# breadboard_rev06_resized-2.net
KiCad netlist of a schematic drawn in EAGLE
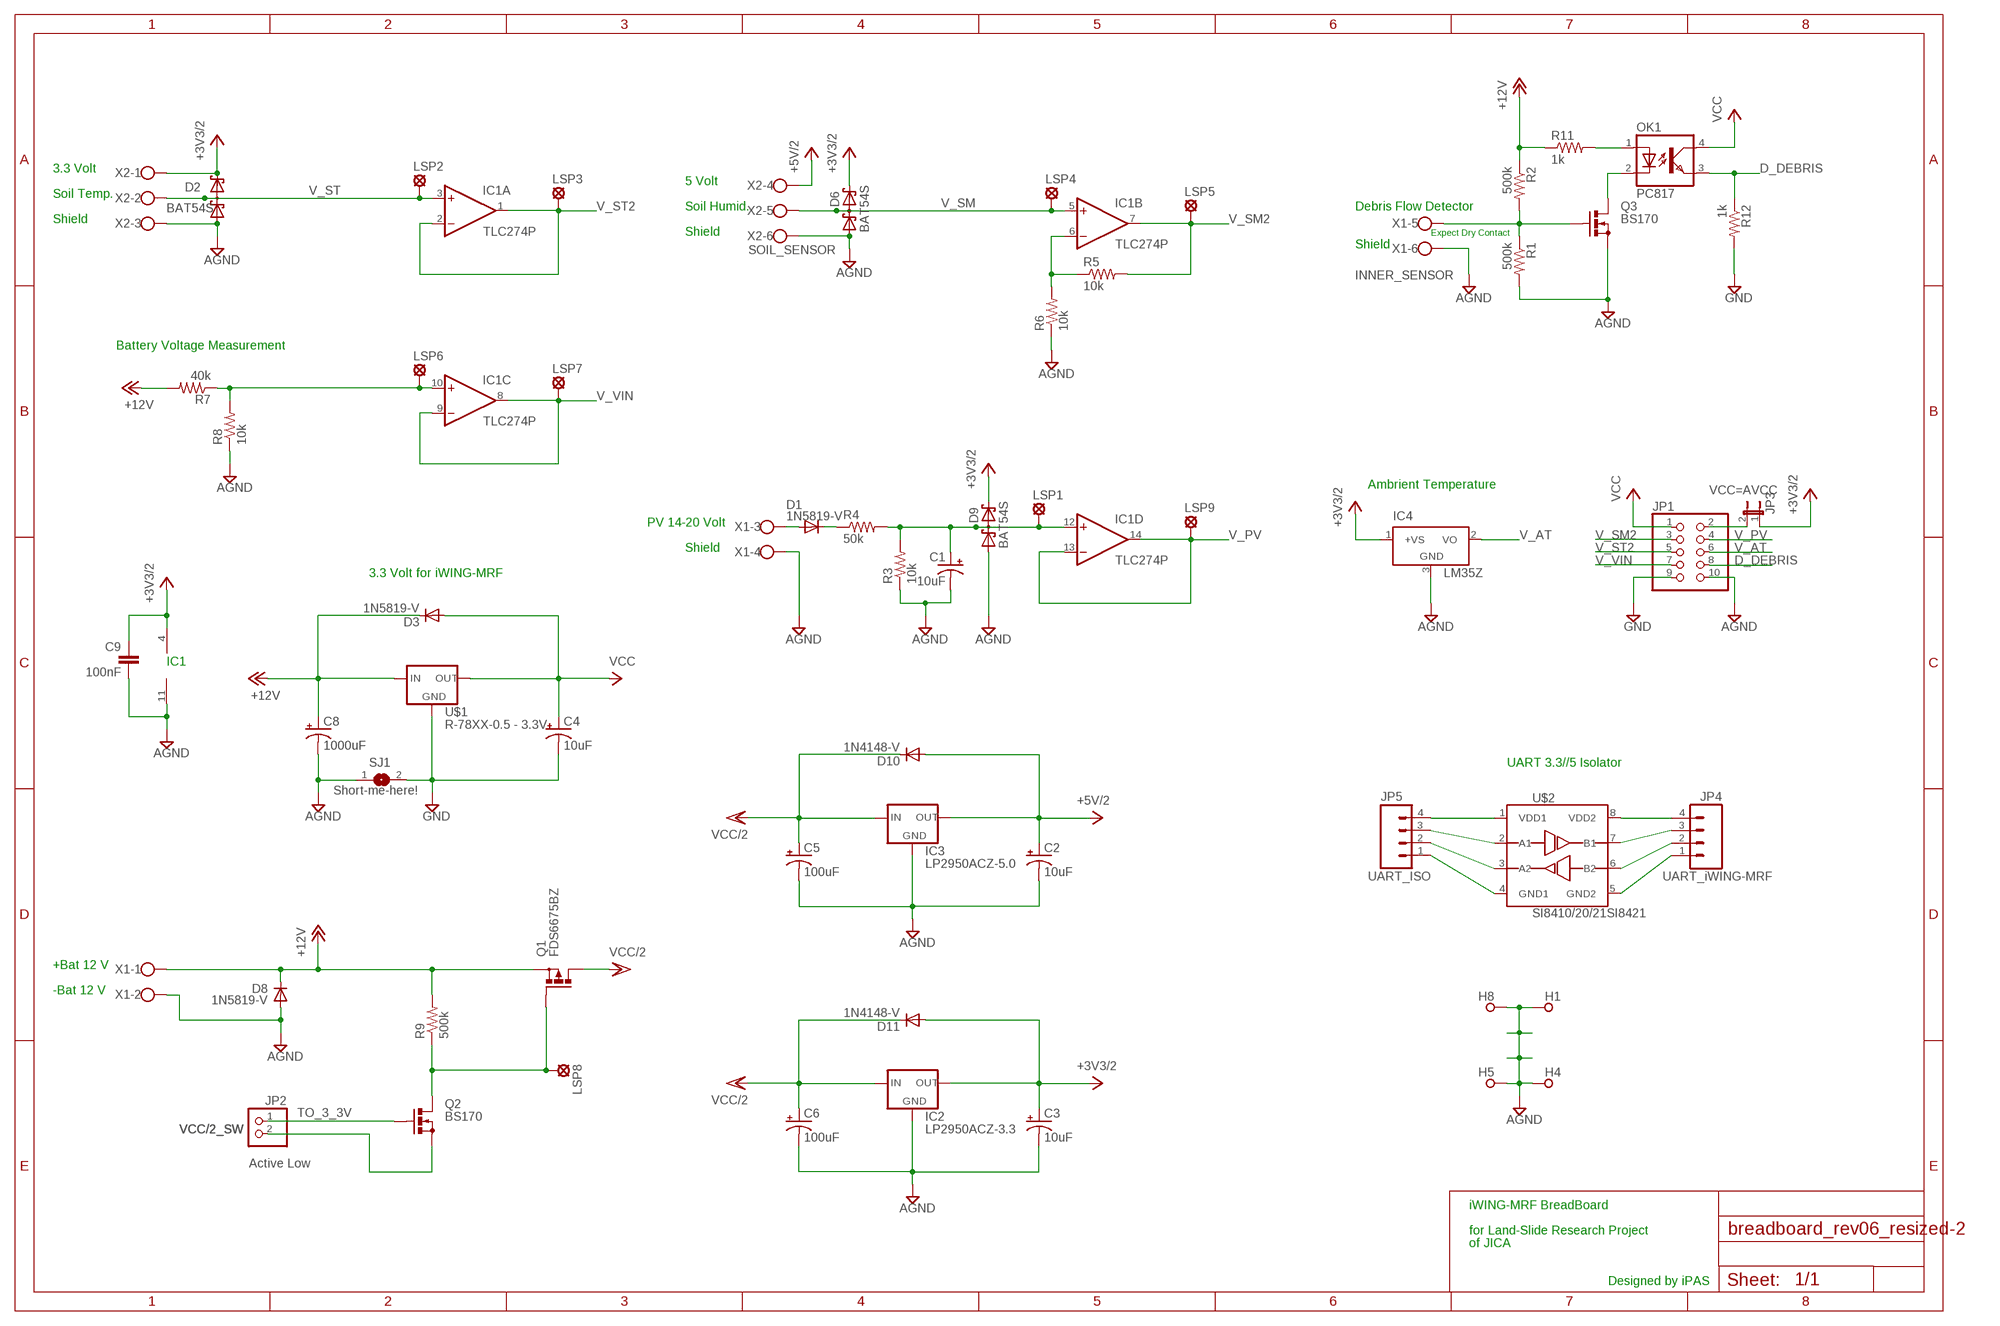
[diagram p0: schematic, sheet 1]

(export (version "E")
  (design (tool "Eeschema 10.0.6"))
  (components
    (comp (ref "C1")
      (value "10uF")
      (footprint "eagle-import:RCL_E2,5-7")
      (libsource (lib "eagle-import") (part "RCL_CPOL-USE2.5-7"))
    )
    (comp (ref "C2")
      (value "10uF")
      (footprint "eagle-import:RCL_E2,5-7")
      (libsource (lib "eagle-import") (part "RCL_CPOL-USE2.5-7"))
    )
    (comp (ref "C3")
      (value "10uF")
      (footprint "eagle-import:RCL_E2,5-7")
      (libsource (lib "eagle-import") (part "RCL_CPOL-USE2.5-7"))
    )
    (comp (ref "C4")
      (value "10uF")
      (footprint "eagle-import:RCL_E2,5-7")
      (libsource (lib "eagle-import") (part "RCL_CPOL-USE2.5-7"))
    )
    (comp (ref "C5")
      (value "100uF")
      (footprint "eagle-import:RCL_E2,5-7")
      (libsource (lib "eagle-import") (part "RCL_CPOL-USE2.5-7"))
    )
    (comp (ref "C6")
      (value "100uF")
      (footprint "eagle-import:RCL_E2,5-7")
      (libsource (lib "eagle-import") (part "RCL_CPOL-USE2.5-7"))
    )
    (comp (ref "C8")
      (value "1000uF")
      (footprint "eagle-import:RCL_E5-13")
      (libsource (lib "eagle-import") (part "RCL_CPOL-USE5-13"))
    )
    (comp (ref "C9")
      (value "100nF")
      (footprint "eagle-import:RCL_C050-025X075")
      (libsource (lib "eagle-import") (part "RCL_C-EU050-025X075"))
    )
    (comp (ref "D1")
      (value "1N5819-V")
      (footprint "eagle-import:DO41-150V")
      (libsource (lib "eagle-import") (part "1N5819-V"))
    )
    (comp (ref "D2")
      (value "BAT54S")
      (footprint "eagle-import:SOT23")
      (libsource (lib "eagle-import") (part "BAT54S"))
    )
    (comp (ref "D3")
      (value "1N5819-V")
      (footprint "eagle-import:DO41-150V")
      (libsource (lib "eagle-import") (part "1N5819-V"))
    )
    (comp (ref "D6")
      (value "BAT54S")
      (footprint "eagle-import:SOT23")
      (libsource (lib "eagle-import") (part "BAT54S"))
    )
    (comp (ref "D8")
      (value "1N5819-V")
      (footprint "eagle-import:DO41-150V")
      (libsource (lib "eagle-import") (part "1N5819-V"))
    )
    (comp (ref "D9")
      (value "BAT54S")
      (footprint "eagle-import:SOT23")
      (libsource (lib "eagle-import") (part "BAT54S"))
    )
    (comp (ref "D10")
      (value "1N4148-V")
      (footprint "eagle-import:DO35-100V")
      (libsource (lib "eagle-import") (part "1N4148-V"))
    )
    (comp (ref "D11")
      (value "1N4148-V")
      (footprint "eagle-import:DO35-100V")
      (libsource (lib "eagle-import") (part "1N4148-V"))
    )
    (comp (ref "H1")
      (value "SPECIAL_DRILL_0.1560")
      (footprint "eagle-import:PAD_0.1560")
      (libsource (lib "eagle-import") (part "SPECIAL_DRILL_0.1560"))
    )
    (comp (ref "H4")
      (value "SPECIAL_DRILL_0.1560")
      (footprint "eagle-import:PAD_0.1560")
      (libsource (lib "eagle-import") (part "SPECIAL_DRILL_0.1560"))
    )
    (comp (ref "H5")
      (value "SPECIAL_DRILL_0.1560")
      (footprint "eagle-import:PAD_0.1560")
      (libsource (lib "eagle-import") (part "SPECIAL_DRILL_0.1560"))
    )
    (comp (ref "H8")
      (value "SPECIAL_DRILL_0.1560")
      (footprint "eagle-import:PAD_0.1560")
      (libsource (lib "eagle-import") (part "SPECIAL_DRILL_0.1560"))
    )
    (comp (ref "IC1")
      (value "TLC274P")
      (footprint "eagle-import:DIL14")
      (libsource (lib "eagle-import") (part "TLC274P"))
    )
    (comp (ref "IC2")
      (value "LP2950ACZ-3.3")
      (footprint "eagle-import:TO92")
      (libsource (lib "eagle-import") (part "LP2950?ACZ-3.3"))
    )
    (comp (ref "IC3")
      (value "LP2950ACZ-5.0")
      (footprint "eagle-import:TO92")
      (libsource (lib "eagle-import") (part "LP2950?ACZ-5.0"))
    )
    (comp (ref "IC4")
      (value "LM35Z")
      (footprint "eagle-import:TO92")
      (libsource (lib "eagle-import") (part "LM35?Z"))
    )
    (comp (ref "JP1")
      (value "HEADER-2X5")
      (footprint "eagle-import:2X05")
      (libsource (lib "eagle-import") (part "HEADER-2X5"))
    )
    (comp (ref "JP2")
      (value "Active Low")
      (footprint "eagle-import:1X02")
      (libsource (lib "eagle-import") (part "PINHD-1X2"))
    )
    (comp (ref "JP3")
      (value "VCC=AVCC")
      (footprint "eagle-import:JUMPER_JP1")
      (libsource (lib "eagle-import") (part "JP1E"))
    )
    (comp (ref "JP4")
      (value "UART_iWING-MRF")
      (footprint "eagle-import:MOLEX-1X4")
      (libsource (lib "eagle-import") (part "M04POLAR"))
    )
    (comp (ref "JP5")
      (value "UART_ISO")
      (footprint "eagle-import:MOLEX-1X4")
      (libsource (lib "eagle-import") (part "M04POLAR"))
    )
    (comp (ref "LSP1")
      (value "LSP13")
      (footprint "eagle-import:LSP13")
      (libsource (lib "eagle-import") (part "LSP13"))
    )
    (comp (ref "LSP2")
      (value "LSP13")
      (footprint "eagle-import:LSP13")
      (libsource (lib "eagle-import") (part "LSP13"))
    )
    (comp (ref "LSP3")
      (value "LSP13")
      (footprint "eagle-import:LSP13")
      (libsource (lib "eagle-import") (part "LSP13"))
    )
    (comp (ref "LSP4")
      (value "LSP13")
      (footprint "eagle-import:LSP13")
      (libsource (lib "eagle-import") (part "LSP13"))
    )
    (comp (ref "LSP5")
      (value "LSP13")
      (footprint "eagle-import:LSP13")
      (libsource (lib "eagle-import") (part "LSP13"))
    )
    (comp (ref "LSP6")
      (value "LSP13")
      (footprint "eagle-import:LSP13")
      (libsource (lib "eagle-import") (part "LSP13"))
    )
    (comp (ref "LSP7")
      (value "LSP13")
      (footprint "eagle-import:LSP13")
      (libsource (lib "eagle-import") (part "LSP13"))
    )
    (comp (ref "LSP8")
      (value "LSP13")
      (footprint "eagle-import:LSP13")
      (libsource (lib "eagle-import") (part "LSP13"))
    )
    (comp (ref "LSP9")
      (value "LSP13")
      (footprint "eagle-import:LSP13")
      (libsource (lib "eagle-import") (part "LSP13"))
    )
    (comp (ref "OK1")
      (value "PC817")
      (footprint "eagle-import:DIL04")
      (fields (field (name "MPN") "PC817X4J000F"))
      (libsource (lib "eagle-import") (part "PC817"))
    )
    (comp (ref "Q1")
      (value "FDS6675BZ")
      (footprint "eagle-import:SO-08")
      (libsource (lib "eagle-import") (part "P-MOSFET-SO8"))
    )
    (comp (ref "Q2")
      (value "BS170")
      (footprint "eagle-import:SOT54E")
      (libsource (lib "eagle-import") (part "BS170"))
    )
    (comp (ref "Q3")
      (value "BS170")
      (footprint "eagle-import:SOT54E")
      (libsource (lib "eagle-import") (part "BS170"))
    )
    (comp (ref "R1")
      (value "500k")
      (footprint "eagle-import:RCL_0204_7")
      (libsource (lib "eagle-import") (part "RCL_R-US_0204/7"))
    )
    (comp (ref "R2")
      (value "500k")
      (footprint "eagle-import:RCL_0204_7")
      (libsource (lib "eagle-import") (part "RCL_R-US_0204/7"))
    )
    (comp (ref "R3")
      (value "10k")
      (footprint "eagle-import:RCL_0204_7")
      (libsource (lib "eagle-import") (part "RCL_R-US_0204/7"))
    )
    (comp (ref "R4")
      (value "50k")
      (footprint "eagle-import:RCL_0204_7")
      (libsource (lib "eagle-import") (part "RCL_R-US_0204/7"))
    )
    (comp (ref "R5")
      (value "10k")
      (footprint "eagle-import:RCL_0204_7")
      (libsource (lib "eagle-import") (part "RCL_R-US_0204/7"))
    )
    (comp (ref "R6")
      (value "10k")
      (footprint "eagle-import:RCL_0204_7")
      (libsource (lib "eagle-import") (part "RCL_R-US_0204/7"))
    )
    (comp (ref "R7")
      (value "40k")
      (footprint "eagle-import:RCL_0204_7")
      (libsource (lib "eagle-import") (part "RCL_R-US_0204/7"))
    )
    (comp (ref "R8")
      (value "10k")
      (footprint "eagle-import:RCL_0204_7")
      (libsource (lib "eagle-import") (part "RCL_R-US_0204/7"))
    )
    (comp (ref "R9")
      (value "500k")
      (footprint "eagle-import:RCL_0204_7")
      (libsource (lib "eagle-import") (part "RCL_R-US_0204/7"))
    )
    (comp (ref "R11")
      (value "1k")
      (footprint "eagle-import:RCL_0204_7")
      (libsource (lib "eagle-import") (part "RCL_R-US_0204/7"))
    )
    (comp (ref "R12")
      (value "1k")
      (footprint "eagle-import:RCL_0204_7")
      (libsource (lib "eagle-import") (part "RCL_R-US_0204/7"))
    )
    (comp (ref "SJ1")
      (value "Short-me-here!")
      (footprint "eagle-import:SJ")
      (libsource (lib "eagle-import") (part "SJ"))
    )
    (comp (ref "U$1")
      (value "R-78XX-0.5 - 3.3V")
      (footprint "eagle-import:SIP3")
      (libsource (lib "eagle-import") (part "R-78XX-0.5"))
    )
    (comp (ref "U$2")
      (value "SI8410/20/21SI8421")
      (footprint "eagle-import:SO-08")
      (libsource (lib "eagle-import") (part "SI8410/20/21SI8421"))
    )
    (comp (ref "X1")
      (value "INNER_SENSOR")
      (footprint "eagle-import:5EHDRC-6P")
      (libsource (lib "eagle-import") (part "5EHDRC-6P"))
    )
    (comp (ref "X2")
      (value "SOIL_SENSOR")
      (footprint "eagle-import:5EHDRC-6P")
      (libsource (lib "eagle-import") (part "5EHDRC-6P"))
    )
  )
  (nets
    (net (code "1") (name "+3V3{slash}2") (class "Default")
      (node (ref "C3") (pin "+") (pinfunction "+_+") (pintype "passive"))
      (node (ref "C9") (pin "1") (pinfunction "1_1") (pintype "passive"))
      (node (ref "D11") (pin "A") (pinfunction "A_A") (pintype "passive"))
      (node (ref "D2") (pin "2") (pinfunction "C2_2") (pintype "passive"))
      (node (ref "D6") (pin "2") (pinfunction "C2_2") (pintype "passive"))
      (node (ref "D9") (pin "2") (pinfunction "C2_2") (pintype "passive"))
      (node (ref "IC1") (pin "4") (pinfunction "V+_4") (pintype "power_in"))
      (node (ref "IC2") (pin "1") (pinfunction "OUT_1") (pintype "passive"))
      (node (ref "IC4") (pin "1") (pinfunction "+VS_1") (pintype "input"))
      (node (ref "JP3") (pin "1") (pinfunction "1_1") (pintype "passive"))
      (node (ref "X2") (pin "1") (pinfunction "KL_1") (pintype "passive"))
    )
    (net (code "2") (name "+5V{slash}2") (class "Default")
      (node (ref "C2") (pin "+") (pinfunction "+_+") (pintype "passive"))
      (node (ref "D10") (pin "A") (pinfunction "A_A") (pintype "passive"))
      (node (ref "IC3") (pin "1") (pinfunction "OUT_1") (pintype "passive"))
      (node (ref "X2") (pin "4") (pinfunction "KL_4") (pintype "passive"))
    )
    (net (code "3") (name "+12V") (class "Default")
      (node (ref "C8") (pin "+") (pinfunction "+_+") (pintype "passive"))
      (node (ref "D3") (pin "C") (pinfunction "C_C") (pintype "passive"))
      (node (ref "D8") (pin "C") (pinfunction "C_C") (pintype "passive"))
      (node (ref "Q1") (pin "1") (pinfunction "S_1") (pintype "passive"))
      (node (ref "Q1") (pin "2") (pinfunction "S_2") (pintype "passive"))
      (node (ref "Q1") (pin "3") (pinfunction "S_3") (pintype "passive"))
      (node (ref "R11") (pin "1") (pinfunction "1_1") (pintype "passive"))
      (node (ref "R2") (pin "1") (pinfunction "1_1") (pintype "passive"))
      (node (ref "R7") (pin "2") (pinfunction "2_2") (pintype "passive"))
      (node (ref "R9") (pin "2") (pinfunction "2_2") (pintype "passive"))
      (node (ref "U$1") (pin "1") (pinfunction "IN_1") (pintype "input"))
      (node (ref "X1") (pin "1") (pinfunction "KL_1") (pintype "passive"))
    )
    (net (code "4") (name "/D_DEBRIS") (class "Default")
      (node (ref "JP1") (pin "8") (pinfunction "8_8") (pintype "passive"))
      (node (ref "OK1") (pin "3") (pinfunction "EMIT_3") (pintype "passive"))
      (node (ref "R12") (pin "1") (pinfunction "1_1") (pintype "passive"))
    )
    (net (code "5") (name "/TO_3_3V") (class "Default")
      (node (ref "JP2") (pin "1") (pinfunction "1_1") (pintype "passive"))
      (node (ref "Q2") (pin "G") (pinfunction "G_G") (pintype "passive"))
    )
    (net (code "6") (name "/VCC{slash}2_SW") (class "Default")
      (node (ref "JP2") (pin "2") (pinfunction "2_2") (pintype "passive"))
      (node (ref "Q2") (pin "S") (pinfunction "S_S") (pintype "passive"))
    )
    (net (code "7") (name "/V_AT") (class "Default")
      (node (ref "IC4") (pin "2") (pinfunction "VO_2") (pintype "output"))
      (node (ref "JP1") (pin "6") (pinfunction "6_6") (pintype "passive"))
    )
    (net (code "8") (name "/V_PV") (class "Default")
      (node (ref "IC1") (pin "13") (pinfunction "-IN_13") (pintype "input"))
      (node (ref "IC1") (pin "14") (pinfunction "OUT_14") (pintype "output"))
      (node (ref "JP1") (pin "4") (pinfunction "4_4") (pintype "passive"))
      (node (ref "LSP9") (pin "MP") (pinfunction "MP_MP") (pintype "passive"))
    )
    (net (code "9") (name "/V_SM") (class "Default")
      (node (ref "D6") (pin "3") (pinfunction "C1A2_3") (pintype "passive"))
      (node (ref "IC1") (pin "5") (pinfunction "+IN_5") (pintype "input"))
      (node (ref "LSP4") (pin "MP") (pinfunction "MP_MP") (pintype "passive"))
      (node (ref "X2") (pin "5") (pinfunction "KL_5") (pintype "passive"))
    )
    (net (code "10") (name "/V_SM2") (class "Default")
      (node (ref "IC1") (pin "7") (pinfunction "OUT_7") (pintype "output"))
      (node (ref "JP1") (pin "3") (pinfunction "3_3") (pintype "passive"))
      (node (ref "LSP5") (pin "MP") (pinfunction "MP_MP") (pintype "passive"))
      (node (ref "R5") (pin "2") (pinfunction "2_2") (pintype "passive"))
    )
    (net (code "11") (name "/V_ST") (class "Default")
      (node (ref "D2") (pin "3") (pinfunction "C1A2_3") (pintype "passive"))
      (node (ref "IC1") (pin "3") (pinfunction "+IN_3") (pintype "input"))
      (node (ref "LSP2") (pin "MP") (pinfunction "MP_MP") (pintype "passive"))
      (node (ref "X2") (pin "2") (pinfunction "KL_2") (pintype "passive"))
    )
    (net (code "12") (name "/V_ST2") (class "Default")
      (node (ref "IC1") (pin "1") (pinfunction "OUT_1") (pintype "output"))
      (node (ref "IC1") (pin "2") (pinfunction "-IN_2") (pintype "input"))
      (node (ref "JP1") (pin "5") (pinfunction "5_5") (pintype "passive"))
      (node (ref "LSP3") (pin "MP") (pinfunction "MP_MP") (pintype "passive"))
    )
    (net (code "13") (name "/V_VIN") (class "Default")
      (node (ref "IC1") (pin "8") (pinfunction "OUT_8") (pintype "output"))
      (node (ref "IC1") (pin "9") (pinfunction "-IN_9") (pintype "input"))
      (node (ref "JP1") (pin "7") (pinfunction "7_7") (pintype "passive"))
      (node (ref "LSP7") (pin "MP") (pinfunction "MP_MP") (pintype "passive"))
    )
    (net (code "14") (name "AGND") (class "Default")
      (node (ref "C1") (pin "-") (pinfunction "-_-") (pintype "passive"))
      (node (ref "C2") (pin "-") (pinfunction "-_-") (pintype "passive"))
      (node (ref "C3") (pin "-") (pinfunction "-_-") (pintype "passive"))
      (node (ref "C5") (pin "-") (pinfunction "-_-") (pintype "passive"))
      (node (ref "C6") (pin "-") (pinfunction "-_-") (pintype "passive"))
      (node (ref "C8") (pin "-") (pinfunction "-_-") (pintype "passive"))
      (node (ref "C9") (pin "2") (pinfunction "2_2") (pintype "passive"))
      (node (ref "D2") (pin "1") (pinfunction "A1_1") (pintype "passive"))
      (node (ref "D6") (pin "1") (pinfunction "A1_1") (pintype "passive"))
      (node (ref "D8") (pin "A") (pinfunction "A_A") (pintype "passive"))
      (node (ref "D9") (pin "1") (pinfunction "A1_1") (pintype "passive"))
      (node (ref "H1") (pin "1") (pinfunction "1_1") (pintype "passive"))
      (node (ref "H4") (pin "1") (pinfunction "1_1") (pintype "passive"))
      (node (ref "H5") (pin "1") (pinfunction "1_1") (pintype "passive"))
      (node (ref "H8") (pin "1") (pinfunction "1_1") (pintype "passive"))
      (node (ref "IC1") (pin "11") (pinfunction "V-_11") (pintype "power_in"))
      (node (ref "IC2") (pin "2") (pinfunction "GND_2") (pintype "input"))
      (node (ref "IC3") (pin "2") (pinfunction "GND_2") (pintype "input"))
      (node (ref "IC4") (pin "3") (pinfunction "GND_3") (pintype "power_in"))
      (node (ref "JP1") (pin "10") (pinfunction "10_10") (pintype "passive"))
      (node (ref "Q3") (pin "S") (pinfunction "S_S") (pintype "passive"))
      (node (ref "R1") (pin "2") (pinfunction "2_2") (pintype "passive"))
      (node (ref "R3") (pin "1") (pinfunction "1_1") (pintype "passive"))
      (node (ref "R6") (pin "1") (pinfunction "1_1") (pintype "passive"))
      (node (ref "R8") (pin "1") (pinfunction "1_1") (pintype "passive"))
      (node (ref "SJ1") (pin "1") (pinfunction "1_1") (pintype "passive"))
      (node (ref "X1") (pin "2") (pinfunction "KL_2") (pintype "passive"))
      (node (ref "X1") (pin "4") (pinfunction "KL_4") (pintype "passive"))
      (node (ref "X1") (pin "6") (pinfunction "KL_6") (pintype "passive"))
      (node (ref "X2") (pin "3") (pinfunction "KL_3") (pintype "passive"))
      (node (ref "X2") (pin "6") (pinfunction "KL_6") (pintype "passive"))
    )
    (net (code "15") (name "GND") (class "Default")
      (node (ref "C4") (pin "-") (pinfunction "-_-") (pintype "passive"))
      (node (ref "JP1") (pin "9") (pinfunction "9_9") (pintype "passive"))
      (node (ref "R12") (pin "2") (pinfunction "2_2") (pintype "passive"))
      (node (ref "SJ1") (pin "2") (pinfunction "2_2") (pintype "passive"))
      (node (ref "U$1") (pin "2") (pinfunction "GND_2") (pintype "input"))
    )
    (net (code "16") (name "Net-(D1-PadC)") (class "Default")
      (node (ref "D1") (pin "C") (pinfunction "C_C") (pintype "passive"))
      (node (ref "R4") (pin "1") (pinfunction "1_1") (pintype "passive"))
    )
    (net (code "17") (name "Net-(D9-C1A2)") (class "Default")
      (node (ref "C1") (pin "+") (pinfunction "+_+") (pintype "passive"))
      (node (ref "D9") (pin "3") (pinfunction "C1A2_3") (pintype "passive"))
      (node (ref "IC1") (pin "12") (pinfunction "+IN_12") (pintype "input"))
      (node (ref "LSP1") (pin "MP") (pinfunction "MP_MP") (pintype "passive"))
      (node (ref "R3") (pin "2") (pinfunction "2_2") (pintype "passive"))
      (node (ref "R4") (pin "2") (pinfunction "2_2") (pintype "passive"))
    )
    (net (code "18") (name "Net-(IC1B--IN)") (class "Default")
      (node (ref "IC1") (pin "6") (pinfunction "-IN_6") (pintype "input"))
      (node (ref "R5") (pin "1") (pinfunction "1_1") (pintype "passive"))
      (node (ref "R6") (pin "2") (pinfunction "2_2") (pintype "passive"))
    )
    (net (code "19") (name "Net-(IC1C-+IN)") (class "Default")
      (node (ref "IC1") (pin "10") (pinfunction "+IN_10") (pintype "input"))
      (node (ref "LSP6") (pin "MP") (pinfunction "MP_MP") (pintype "passive"))
      (node (ref "R7") (pin "1") (pinfunction "1_1") (pintype "passive"))
      (node (ref "R8") (pin "2") (pinfunction "2_2") (pintype "passive"))
    )
    (net (code "20") (name "Net-(JP1-Pad2)") (class "Default")
      (node (ref "JP1") (pin "2") (pinfunction "2_2") (pintype "passive"))
      (node (ref "JP3") (pin "2") (pinfunction "2_2") (pintype "passive"))
    )
    (net (code "21") (name "Net-(OK1-A)") (class "Default")
      (node (ref "OK1") (pin "1") (pinfunction "A_1") (pintype "passive"))
      (node (ref "R11") (pin "2") (pinfunction "2_2") (pintype "passive"))
    )
    (net (code "22") (name "Net-(OK1-C)") (class "Default")
      (node (ref "OK1") (pin "2") (pinfunction "C_2") (pintype "passive"))
      (node (ref "Q3") (pin "D") (pinfunction "D_D") (pintype "passive"))
    )
    (net (code "23") (name "Net-(Q1-G)") (class "Default")
      (node (ref "LSP8") (pin "MP") (pinfunction "MP_MP") (pintype "passive"))
      (node (ref "Q1") (pin "4") (pinfunction "G_4") (pintype "passive"))
      (node (ref "Q2") (pin "D") (pinfunction "D_D") (pintype "passive"))
      (node (ref "R9") (pin "1") (pinfunction "1_1") (pintype "passive"))
    )
    (net (code "24") (name "Net-(U$2-A1)") (class "Default")
      (node (ref "JP5") (pin "3") (pinfunction "3_3") (pintype "passive"))
      (node (ref "U$2") (pin "2") (pinfunction "A1_2") (pintype "input"))
    )
    (net (code "25") (name "Net-(U$2-A2)") (class "Default")
      (node (ref "JP5") (pin "2") (pinfunction "2_2") (pintype "passive"))
      (node (ref "U$2") (pin "3") (pinfunction "A2_3") (pintype "output"))
    )
    (net (code "26") (name "Net-(U$2-B1)") (class "Default")
      (node (ref "JP4") (pin "3") (pinfunction "3_3") (pintype "passive"))
      (node (ref "U$2") (pin "7") (pinfunction "B1_7") (pintype "output"))
    )
    (net (code "27") (name "Net-(U$2-B2)") (class "Default")
      (node (ref "JP4") (pin "2") (pinfunction "2_2") (pintype "passive"))
      (node (ref "U$2") (pin "6") (pinfunction "B2_6") (pintype "input"))
    )
    (net (code "28") (name "Net-(U$2-GND1)") (class "Default")
      (node (ref "JP5") (pin "1") (pinfunction "1_1") (pintype "passive"))
      (node (ref "U$2") (pin "4") (pinfunction "GND1_4") (pintype "power_in"))
    )
    (net (code "29") (name "Net-(U$2-GND2)") (class "Default")
      (node (ref "JP4") (pin "1") (pinfunction "1_1") (pintype "passive"))
      (node (ref "U$2") (pin "5") (pinfunction "GND2_5") (pintype "power_in"))
    )
    (net (code "30") (name "Net-(U$2-VDD1)") (class "Default")
      (node (ref "JP5") (pin "4") (pinfunction "4_4") (pintype "passive"))
      (node (ref "U$2") (pin "1") (pinfunction "VDD1_1") (pintype "power_in"))
    )
    (net (code "31") (name "Net-(U$2-VDD2)") (class "Default")
      (node (ref "JP4") (pin "4") (pinfunction "4_4") (pintype "passive"))
      (node (ref "U$2") (pin "8") (pinfunction "VDD2_8") (pintype "power_in"))
    )
    (net (code "32") (name "Net-(X1C-KL)") (class "Default")
      (node (ref "D1") (pin "A") (pinfunction "A_A") (pintype "passive"))
      (node (ref "X1") (pin "3") (pinfunction "KL_3") (pintype "passive"))
    )
    (net (code "33") (name "Net-(X1E-KL)") (class "Default")
      (node (ref "Q3") (pin "G") (pinfunction "G_G") (pintype "passive"))
      (node (ref "R1") (pin "1") (pinfunction "1_1") (pintype "passive"))
      (node (ref "R2") (pin "2") (pinfunction "2_2") (pintype "passive"))
      (node (ref "X1") (pin "5") (pinfunction "KL_5") (pintype "passive"))
    )
    (net (code "34") (name "VCC") (class "Default")
      (node (ref "C4") (pin "+") (pinfunction "+_+") (pintype "passive"))
      (node (ref "D3") (pin "A") (pinfunction "A_A") (pintype "passive"))
      (node (ref "JP1") (pin "1") (pinfunction "1_1") (pintype "passive"))
      (node (ref "OK1") (pin "4") (pinfunction "COL_4") (pintype "passive"))
      (node (ref "U$1") (pin "3") (pinfunction "OUT_3") (pintype "passive"))
    )
    (net (code "35") (name "VCC{slash}2") (class "Default")
      (node (ref "C5") (pin "+") (pinfunction "+_+") (pintype "passive"))
      (node (ref "C6") (pin "+") (pinfunction "+_+") (pintype "passive"))
      (node (ref "D10") (pin "C") (pinfunction "C_C") (pintype "passive"))
      (node (ref "D11") (pin "C") (pinfunction "C_C") (pintype "passive"))
      (node (ref "IC2") (pin "3") (pinfunction "IN_3") (pintype "input"))
      (node (ref "IC3") (pin "3") (pinfunction "IN_3") (pintype "input"))
      (node (ref "Q1") (pin "5") (pinfunction "D_5") (pintype "passive"))
      (node (ref "Q1") (pin "6") (pinfunction "D_6") (pintype "passive"))
      (node (ref "Q1") (pin "7") (pinfunction "D_7") (pintype "passive"))
      (node (ref "Q1") (pin "8") (pinfunction "D_8") (pintype "passive"))
    )
  )
)
